# Soldering_Iron_Light_Schematic.net
KiCad netlist of a schematic drawn in EAGLE
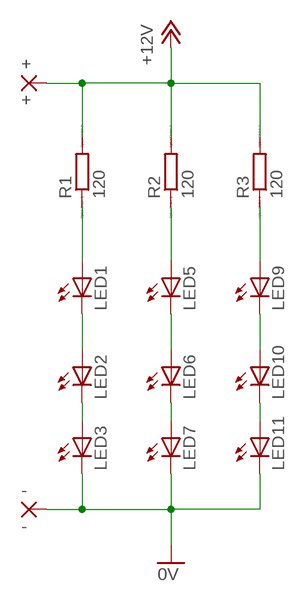
[diagram p0: schematic, sheet 1]

(export (version "E")
  (design (tool "Eeschema 10.0.6"))
  (components
    (comp (ref "+")
      (value "+")
      (footprint "eagle-import:SMD1,27-2,54")
      (libsource (lib "eagle-import") (part "SMD2"))
    )
    (comp (ref "-")
      (value "-")
      (footprint "eagle-import:SMD1,27-2,54")
      (libsource (lib "eagle-import") (part "SMD2"))
    )
    (comp (ref "LED1")
      (value "LEDCHIPLED_1206")
      (footprint "eagle-import:CHIPLED_1206")
      (libsource (lib "eagle-import") (part "LEDCHIPLED_1206"))
    )
    (comp (ref "LED2")
      (value "LEDCHIPLED_1206")
      (footprint "eagle-import:CHIPLED_1206")
      (libsource (lib "eagle-import") (part "LEDCHIPLED_1206"))
    )
    (comp (ref "LED3")
      (value "LEDCHIPLED_1206")
      (footprint "eagle-import:CHIPLED_1206")
      (libsource (lib "eagle-import") (part "LEDCHIPLED_1206"))
    )
    (comp (ref "LED5")
      (value "LEDCHIPLED_1206")
      (footprint "eagle-import:CHIPLED_1206")
      (libsource (lib "eagle-import") (part "LEDCHIPLED_1206"))
    )
    (comp (ref "LED6")
      (value "LEDCHIPLED_1206")
      (footprint "eagle-import:CHIPLED_1206")
      (libsource (lib "eagle-import") (part "LEDCHIPLED_1206"))
    )
    (comp (ref "LED7")
      (value "LEDCHIPLED_1206")
      (footprint "eagle-import:CHIPLED_1206")
      (libsource (lib "eagle-import") (part "LEDCHIPLED_1206"))
    )
    (comp (ref "LED9")
      (value "LEDCHIPLED_1206")
      (footprint "eagle-import:CHIPLED_1206")
      (libsource (lib "eagle-import") (part "LEDCHIPLED_1206"))
    )
    (comp (ref "LED10")
      (value "LEDCHIPLED_1206")
      (footprint "eagle-import:CHIPLED_1206")
      (libsource (lib "eagle-import") (part "LEDCHIPLED_1206"))
    )
    (comp (ref "LED11")
      (value "LEDCHIPLED_1206")
      (footprint "eagle-import:CHIPLED_1206")
      (libsource (lib "eagle-import") (part "LEDCHIPLED_1206"))
    )
    (comp (ref "R1")
      (value "120")
      (footprint "eagle-import:R0805")
      (libsource (lib "eagle-import") (part "R"))
    )
    (comp (ref "R2")
      (value "120")
      (footprint "eagle-import:R0805")
      (libsource (lib "eagle-import") (part "R"))
    )
    (comp (ref "R3")
      (value "120")
      (footprint "eagle-import:R0805")
      (libsource (lib "eagle-import") (part "R"))
    )
  )
  (nets
    (net (code "1") (name "+12V") (class "Default")
      (node (ref "+") (pin "1") (pinfunction "P_1") (pintype "passive"))
      (node (ref "R1") (pin "2") (pinfunction "2_2") (pintype "passive"))
      (node (ref "R2") (pin "2") (pinfunction "2_2") (pintype "passive"))
      (node (ref "R3") (pin "2") (pinfunction "2_2") (pintype "passive"))
    )
    (net (code "2") (name "0V") (class "Default")
      (node (ref "-") (pin "1") (pinfunction "P_1") (pintype "passive"))
      (node (ref "LED11") (pin "C") (pinfunction "C_C") (pintype "passive"))
      (node (ref "LED3") (pin "C") (pinfunction "C_C") (pintype "passive"))
      (node (ref "LED7") (pin "C") (pinfunction "C_C") (pintype "passive"))
    )
    (net (code "3") (name "Net-(LED1-PadA)") (class "Default")
      (node (ref "LED1") (pin "A") (pinfunction "A_A") (pintype "passive"))
      (node (ref "R1") (pin "1") (pinfunction "1_1") (pintype "passive"))
    )
    (net (code "4") (name "Net-(LED1-PadC)") (class "Default")
      (node (ref "LED1") (pin "C") (pinfunction "C_C") (pintype "passive"))
      (node (ref "LED2") (pin "A") (pinfunction "A_A") (pintype "passive"))
    )
    (net (code "5") (name "Net-(LED2-PadC)") (class "Default")
      (node (ref "LED2") (pin "C") (pinfunction "C_C") (pintype "passive"))
      (node (ref "LED3") (pin "A") (pinfunction "A_A") (pintype "passive"))
    )
    (net (code "6") (name "Net-(LED5-PadA)") (class "Default")
      (node (ref "LED5") (pin "A") (pinfunction "A_A") (pintype "passive"))
      (node (ref "R2") (pin "1") (pinfunction "1_1") (pintype "passive"))
    )
    (net (code "7") (name "Net-(LED5-PadC)") (class "Default")
      (node (ref "LED5") (pin "C") (pinfunction "C_C") (pintype "passive"))
      (node (ref "LED6") (pin "A") (pinfunction "A_A") (pintype "passive"))
    )
    (net (code "8") (name "Net-(LED6-PadC)") (class "Default")
      (node (ref "LED6") (pin "C") (pinfunction "C_C") (pintype "passive"))
      (node (ref "LED7") (pin "A") (pinfunction "A_A") (pintype "passive"))
    )
    (net (code "9") (name "Net-(LED9-PadA)") (class "Default")
      (node (ref "LED9") (pin "A") (pinfunction "A_A") (pintype "passive"))
      (node (ref "R3") (pin "1") (pinfunction "1_1") (pintype "passive"))
    )
    (net (code "10") (name "Net-(LED10-PadA)") (class "Default")
      (node (ref "LED10") (pin "A") (pinfunction "A_A") (pintype "passive"))
      (node (ref "LED9") (pin "C") (pinfunction "C_C") (pintype "passive"))
    )
    (net (code "11") (name "Net-(LED10-PadC)") (class "Default")
      (node (ref "LED10") (pin "C") (pinfunction "C_C") (pintype "passive"))
      (node (ref "LED11") (pin "A") (pinfunction "A_A") (pintype "passive"))
    )
  )
)
